# Charger.net
KiCad netlist of a schematic drawn in Altium Designer
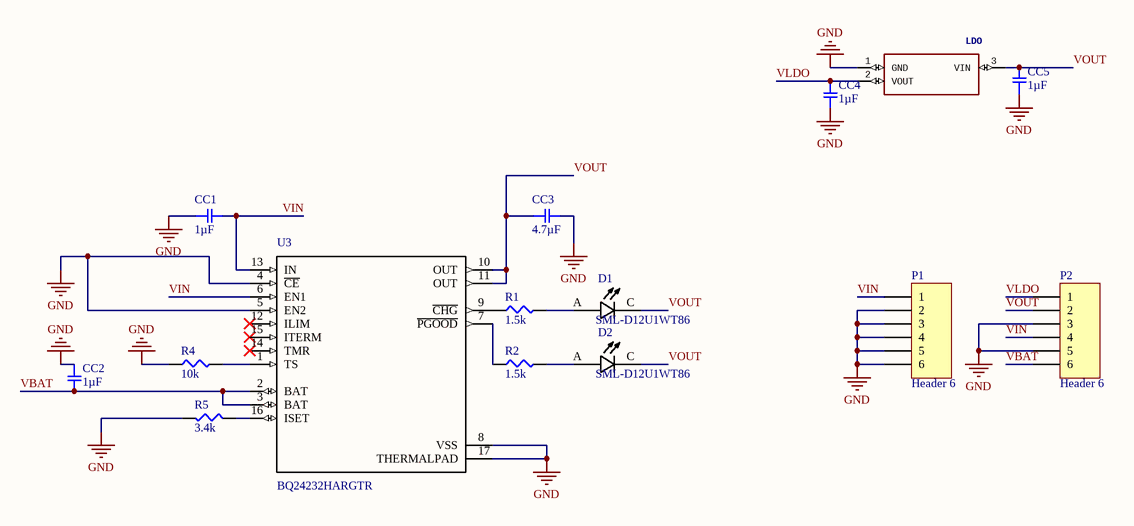
[diagram p0: Charger.SchDoc]

(export (version "E")
  (design (tool "Eeschema 10.0.6"))
  (components
    (comp (ref "CC1")
      (value "1µF")
      (footprint "SMD-0603C")
      (description "CAP CER 1UF 10V X5R 0603")
      (fields
        (field (name "DIGI-KEY PART NUMBER") "490-1543-1-ND")
        (field (name "PART NUMBER") "GRM188R61A105KA61D")
      )
      (libsource (lib "capacitor_murata_0603") (part "GRM188R61A105KA61D"))
    )
    (comp (ref "CC2")
      (value "1µF")
      (footprint "SMD-0603C")
      (description "CAP CER 1UF 10V X5R 0603")
      (fields
        (field (name "DIGI-KEY PART NUMBER") "490-1543-1-ND")
        (field (name "PART NUMBER") "GRM188R61A105KA61D")
      )
      (libsource (lib "capacitor_murata_0603") (part "GRM188R61A105KA61D"))
    )
    (comp (ref "CC3")
      (value "4.7µF")
      (footprint "SMD-0603C")
      (description "CAP CER 4.7UF 4V X5R 0603")
      (fields
        (field (name "DIGI-KEY PART NUMBER") "490-3891-1-ND")
        (field (name "PART NUMBER") "GRM185R60G475ME15D")
      )
      (libsource (lib "capacitor_murata_0603") (part "GRM185R60G475ME15D"))
    )
    (comp (ref "CC4")
      (value "1µF")
      (footprint "SMD-0603C")
      (description "CAP CER 1UF 10V X5R 0603")
      (fields
        (field (name "DIGI-KEY PART NUMBER") "490-1543-1-ND")
        (field (name "PART NUMBER") "GRM188R61A105KA61D")
      )
      (libsource (lib "capacitor_murata_0603") (part "GRM188R61A105KA61D"))
    )
    (comp (ref "CC5")
      (value "1µF")
      (footprint "SMD-0603C")
      (description "CAP CER 1UF 10V X5R 0603")
      (fields
        (field (name "DIGI-KEY PART NUMBER") "490-1543-1-ND")
        (field (name "PART NUMBER") "GRM188R61A105KA61D")
      )
      (libsource (lib "capacitor_murata_0603") (part "GRM188R61A105KA61D"))
    )
    (comp (ref "D1")
      (value "SML-D12U1WT86")
      (footprint "*LED_SML-D12Y1WT86_SML-D12U1WT86(Primary)")
      (description "SML-D12 Series Red 0603 Diffused 63 mcd 2.2 V Surface Mount LED")
      (fields (field (name "DIGI-KEY_PART_NUMBER") "SML-D12U1WT86CT-ND") (field (name "MF") "Rohm"))
      (libsource (lib "SML-D12U1WT86") (part "SML-D12U1WT86"))
    )
    (comp (ref "D2")
      (value "SML-D12U1WT86")
      (footprint "*LED_SML-D12Y1WT86_SML-D12U1WT86(Primary)")
      (description "SML-D12 Series Red 0603 Diffused 63 mcd 2.2 V Surface Mount LED")
      (fields (field (name "DIGI-KEY_PART_NUMBER") "SML-D12U1WT86CT-ND") (field (name "MF") "Rohm"))
      (libsource (lib "SML-D12U1WT86") (part "SML-D12U1WT86"))
    )
    (comp (ref "LDO")
      (value "250mA 3.3V Ultra Low IQ LDO Reg. SOT23 DiodesZetex AP2138N-3.3TRG1, Low Noise LDO Voltage Regulator, 250 (Min)mA, 3.3 V +/-2%, 2.5 to 6.6 Vin, 3-Pin SOT-23Source:  Datasheet")
      (footprint "SOT95P282X145-3N")
      (fields
        (field (name "MANUFACTURER_PART_NUMBER") "AP2138N-3.3TRG1")
        (field (name "MOUSER_PART_NUMBER") "621-AP2138N-3.3TRG1")
        (field (name "RS_PART_NUMBER") "9210398P")
      )
      (libsource (lib "AP2138N-3.3TRG1") (part "AP2138N-3.3TRG1"))
    )
    (comp (ref "P1")
      (value "Header 6")
      (footprint "HDR1X6")
      (description "Header, 6-Pin")
      (fields (field (name "PUBLISHER") "Altium Limited"))
      (libsource (lib "Miscellaneous Connectors") (part "Header 6"))
    )
    (comp (ref "P2")
      (value "Header 6")
      (footprint "HDR1X6")
      (description "Header, 6-Pin")
      (fields (field (name "PUBLISHER") "Altium Limited"))
      (libsource (lib "Miscellaneous Connectors") (part "Header 6"))
    )
    (comp (ref "R1")
      (value "1.5k")
      (footprint "SMD-0603-RES")
      (description "RES SMD 1.5K OHM 1% 1/10W 0603")
      (fields
        (field (name "PART NUMBER") "ERJ-3EKF1501V")
        (field (name "DIGI-KEY PART NUMBER") "P1.50KHCT-ND")
      )
      (libsource (lib "Panasonic_ERJ_0603") (part "ERJ-3EKF1501V"))
    )
    (comp (ref "R2")
      (value "1.5k")
      (footprint "SMD-0603-RES")
      (description "RES SMD 1.5K OHM 1% 1/10W 0603")
      (fields
        (field (name "PART NUMBER") "ERJ-3EKF1501V")
        (field (name "DIGI-KEY PART NUMBER") "P1.50KHCT-ND")
      )
      (libsource (lib "Panasonic_ERJ_0603") (part "ERJ-3EKF1501V"))
    )
    (comp (ref "R4")
      (value "10k")
      (footprint "SMD-0603-RES")
      (description "RES SMD 10K OHM 5% 1/4W 0603")
      (fields (field (name "PART NUMBER") "ERJ-PA3J103V") (field (name "DIGI-KEY PART NUMBER") "P10KBZCT-ND"))
      (libsource (lib "Panasonic_ERJ_0603") (part "ERJ-PA3J103V"))
    )
    (comp (ref "R5")
      (value "3.4k")
      (footprint "SMD-0603-RES")
      (description "RES SMD 3.4K OHM 1% 1/10W 0603")
      (fields
        (field (name "PART NUMBER") "ERJ-3EKF3401V")
        (field (name "DIGI-KEY PART NUMBER") "P3.40KHCT-ND")
      )
      (libsource (lib "Panasonic_ERJ_0603") (part "ERJ-3EKF3401V"))
    )
    (comp (ref "U3")
      (value "BQ24232HARGTR")
      (footprint "*QFN50P300X300X100-17N")
      (fields (field (name "MF") "Texas Instruments") (field (name "DIGI-KEY_PART_NUMBER") "296-49554-1-ND"))
      (libsource (lib "BQ24232HARGTR") (part "BQ24232HARGTR"))
    )
  )
  (nets
    (net (code "1") (name "/VBAT") (class "Default")
      (node (ref "CC2") (pin "2") (pinfunction "2_2") (pintype "passive"))
      (node (ref "P2") (pin "6") (pinfunction "6_6") (pintype "passive"))
      (node (ref "U3") (pin "2") (pinfunction "BAT_2") (pintype "bidirectional"))
      (node (ref "U3") (pin "3") (pinfunction "BAT_3") (pintype "bidirectional"))
    )
    (net (code "2") (name "/VIN") (class "Default")
      (node (ref "CC1") (pin "2") (pinfunction "2_2") (pintype "passive"))
      (node (ref "P1") (pin "1") (pinfunction "1_1") (pintype "passive"))
      (node (ref "P2") (pin "4") (pinfunction "4_4") (pintype "passive"))
      (node (ref "U3") (pin "13") (pinfunction "IN_13") (pintype "input"))
      (node (ref "U3") (pin "6") (pinfunction "EN1_6") (pintype "input"))
    )
    (net (code "3") (name "/VLDO") (class "Default")
      (node (ref "CC4") (pin "1") (pinfunction "1_1") (pintype "passive"))
      (node (ref "LDO") (pin "2") (pinfunction "VOUT_2") (pintype "bidirectional"))
      (node (ref "P2") (pin "1") (pinfunction "1_1") (pintype "passive"))
    )
    (net (code "4") (name "/VOUT") (class "Default")
      (node (ref "CC3") (pin "1") (pinfunction "1_1") (pintype "passive"))
      (node (ref "CC5") (pin "2") (pinfunction "2_2") (pintype "passive"))
      (node (ref "D1") (pin "C") (pinfunction "C_C") (pintype "passive"))
      (node (ref "D2") (pin "C") (pinfunction "C_C") (pintype "passive"))
      (node (ref "LDO") (pin "3") (pinfunction "VIN_3") (pintype "bidirectional"))
      (node (ref "P2") (pin "2") (pinfunction "2_2") (pintype "passive"))
      (node (ref "U3") (pin "10") (pinfunction "OUT_10") (pintype "output"))
      (node (ref "U3") (pin "11") (pinfunction "OUT_11") (pintype "output"))
    )
    (net (code "5") (name "GND") (class "Default")
      (node (ref "CC1") (pin "1") (pinfunction "1_1") (pintype "passive"))
      (node (ref "CC2") (pin "1") (pinfunction "1_1") (pintype "passive"))
      (node (ref "CC3") (pin "2") (pinfunction "2_2") (pintype "passive"))
      (node (ref "CC4") (pin "2") (pinfunction "2_2") (pintype "passive"))
      (node (ref "CC5") (pin "1") (pinfunction "1_1") (pintype "passive"))
      (node (ref "LDO") (pin "1") (pinfunction "GND_1") (pintype "bidirectional"))
      (node (ref "P1") (pin "2") (pinfunction "2_2") (pintype "passive"))
      (node (ref "P1") (pin "3") (pinfunction "3_3") (pintype "passive"))
      (node (ref "P1") (pin "4") (pinfunction "4_4") (pintype "passive"))
      (node (ref "P1") (pin "5") (pinfunction "5_5") (pintype "passive"))
      (node (ref "P1") (pin "6") (pinfunction "6_6") (pintype "passive"))
      (node (ref "P2") (pin "3") (pinfunction "3_3") (pintype "passive"))
      (node (ref "P2") (pin "5") (pinfunction "5_5") (pintype "passive"))
      (node (ref "R4") (pin "1") (pinfunction "1_1") (pintype "passive"))
      (node (ref "R5") (pin "2") (pinfunction "2_2") (pintype "passive"))
      (node (ref "U3") (pin "17") (pinfunction "THERMALPAD_17") (pintype "power_in"))
      (node (ref "U3") (pin "4") (pinfunction "~{CE}_4") (pintype "input"))
      (node (ref "U3") (pin "5") (pinfunction "EN2_5") (pintype "input"))
      (node (ref "U3") (pin "8") (pinfunction "VSS_8") (pintype "power_in"))
    )
    (net (code "6") (name "Net-(D1-PadA)") (class "Default")
      (node (ref "D1") (pin "A") (pinfunction "A_A") (pintype "passive"))
      (node (ref "R1") (pin "2") (pinfunction "2_2") (pintype "passive"))
    )
    (net (code "7") (name "Net-(D2-PadA)") (class "Default")
      (node (ref "D2") (pin "A") (pinfunction "A_A") (pintype "passive"))
      (node (ref "R2") (pin "2") (pinfunction "2_2") (pintype "passive"))
    )
    (net (code "8") (name "Net-(U3-ISET)") (class "Default")
      (node (ref "R5") (pin "1") (pinfunction "1_1") (pintype "passive"))
      (node (ref "U3") (pin "16") (pinfunction "ISET_16") (pintype "bidirectional"))
    )
    (net (code "9") (name "Net-(U3-TS)") (class "Default")
      (node (ref "R4") (pin "2") (pinfunction "2_2") (pintype "passive"))
      (node (ref "U3") (pin "1") (pinfunction "TS_1") (pintype "input"))
    )
    (net (code "10") (name "Net-(U3-~{CHG})") (class "Default")
      (node (ref "R1") (pin "1") (pinfunction "1_1") (pintype "passive"))
      (node (ref "U3") (pin "9") (pinfunction "~{CHG}_9") (pintype "output"))
    )
    (net (code "11") (name "Net-(U3-~{PGOOD})") (class "Default")
      (node (ref "R2") (pin "1") (pinfunction "1_1") (pintype "passive"))
      (node (ref "U3") (pin "7") (pinfunction "~{PGOOD}_7") (pintype "output"))
    )
    (net (code "12") (name "unconnected-(U3-ILIM-Pad12)") (class "Default")
      (node (ref "U3") (pin "12") (pinfunction "ILIM_12") (pintype "input+no_connect"))
    )
    (net (code "13") (name "unconnected-(U3-ITERM-Pad15)") (class "Default")
      (node (ref "U3") (pin "15") (pinfunction "ITERM_15") (pintype "input+no_connect"))
    )
    (net (code "14") (name "unconnected-(U3-TMR-Pad14)") (class "Default")
      (node (ref "U3") (pin "14") (pinfunction "TMR_14") (pintype "input+no_connect"))
    )
  )
)
